# CAN.net
KiCad netlist of a schematic drawn in Altium Designer
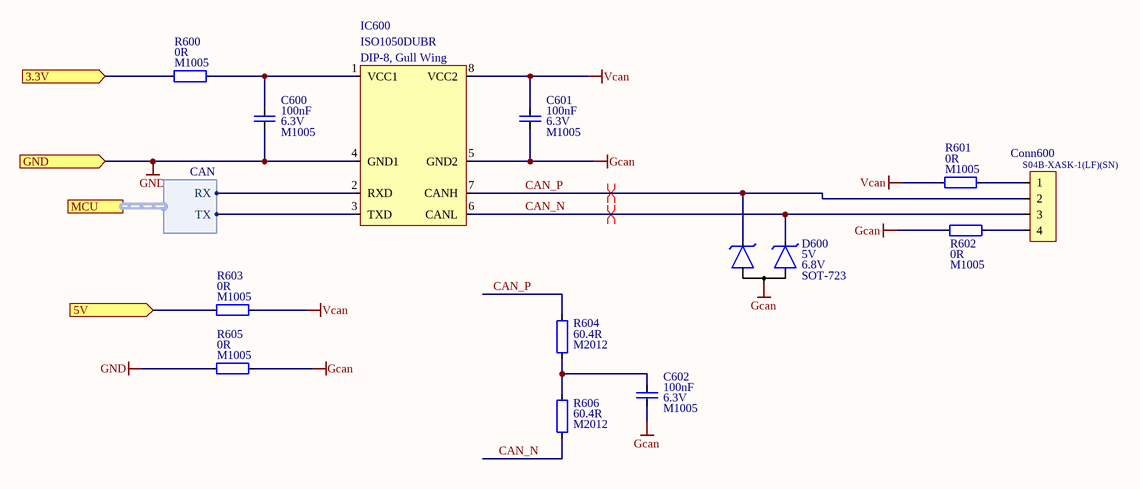
[diagram p0: CAN.SchDoc]

(export (version "E")
  (design (tool "Eeschema 10.0.6"))
  (components
    (comp (ref "C600")
      (value "100nF")
      (footprint "Capacitor_Ceramic_M1005_I0402")
      (description "Cap, Cer, 100nF, 6.3V, M1005")
      (fields
        (field (name "VOLTAGE") "6.3V")
        (field (name "MANUFACTURER PART NUMBER") "04026D104KAT4A")
        (field (name "MANUFACTURER") "Kyocera")
        (field (name "PACKAGE") "M1005")
      )
      (libsource (lib "Capacitor") (part "capacitor_ceramic"))
    )
    (comp (ref "C601")
      (value "100nF")
      (footprint "Capacitor_Ceramic_M1005_I0402")
      (description "Cap, Cer, 100nF, 6.3V, M1005")
      (fields
        (field (name "VOLTAGE") "6.3V")
        (field (name "MANUFACTURER PART NUMBER") "04026D104KAT4A")
        (field (name "MANUFACTURER") "Kyocera")
        (field (name "PACKAGE") "M1005")
      )
      (libsource (lib "Capacitor") (part "capacitor_ceramic"))
    )
    (comp (ref "C602")
      (value "100nF")
      (footprint "Capacitor_Ceramic_M1005_I0402")
      (description "Cap, Cer, 100nF, 6.3V, M1005")
      (fields
        (field (name "VOLTAGE") "6.3V")
        (field (name "MANUFACTURER PART NUMBER") "04026D104KAT4A")
        (field (name "MANUFACTURER") "Kyocera")
        (field (name "PACKAGE") "M1005")
      )
      (libsource (lib "Capacitor") (part "capacitor_ceramic"))
    )
    (comp (ref "Conn600")
      (value "Connector - 4P")
      (footprint "Connector, S04B-XASK-1")
      (description "Conn, JST, 4P, TH, XA, Side Entry")
      (fields
        (field (name "MANUFACTURER") "JST")
        (field (name "MANUFACTURER PART NUMBER") "S04B-XASK-1(LF)(SN)")
      )
      (libsource (lib "Connector - JST") (part "Connector - 4P"))
    )
    (comp (ref "D600")
      (value "Diode_Tvs_2P_Common_Anode")
      (footprint "Diode_SOT-723_2P_Common_Anode_Type_1")
      (description "Diode, TVS, 5V/6.8V, SOD-723")
      (fields
        (field (name "MANUFACTURER PART NUMBER") "DF3A6.8LFV,L3F")
        (field (name "MANUFACTURER") "Toshiba")
        (field (name "VOLTAGE, BREAK DOWN") "6.8V")
        (field (name "VOLTAGE, STAND OFF") "5V")
        (field (name "PACKAGE") "SOT-723")
      )
      (libsource (lib "Diode") (part "Diode_Tvs_2P_Common_Anode"))
    )
    (comp (ref "IC600")
      (value "CAN - Texas, ISO1050DUB")
      (footprint "DIP-8, Gull Wing")
      (description "IC, Interface, CAN, DIP-8, Gull Wing")
      (fields
        (field (name "MANUFACTURER") "Texas")
        (field (name "MANUFACTURER PART NUMBER") "ISO1050DUBR")
        (field (name "PACKAGE") "DIP-8, Gull Wing")
      )
      (libsource (lib "IC-Interface") (part "CAN - Texas, ISO1050DUB"))
    )
    (comp (ref "R600")
      (value "0R")
      (footprint "Resistor_Smd_M1005_I0402")
      (description "Res, 0R, M1005")
      (fields
        (field (name "MANUFACTURER") "Yageo")
        (field (name "MANUFACTURER PART NUMBER") "RC0402FR-070RL")
        (field (name "PACKAGE") "M1005")
      )
      (libsource (lib "Resistor") (part "Resistor"))
    )
    (comp (ref "R601")
      (value "0R")
      (footprint "Resistor_Smd_M1005_I0402")
      (description "Res, 0R, M1005")
      (fields
        (field (name "MANUFACTURER") "Yageo")
        (field (name "MANUFACTURER PART NUMBER") "RC0402FR-070RL")
        (field (name "PACKAGE") "M1005")
      )
      (libsource (lib "Resistor") (part "Resistor"))
    )
    (comp (ref "R602")
      (value "0R")
      (footprint "Resistor_Smd_M1005_I0402")
      (description "Res, 0R, M1005")
      (fields
        (field (name "MANUFACTURER") "Yageo")
        (field (name "MANUFACTURER PART NUMBER") "RC0402FR-070RL")
        (field (name "PACKAGE") "M1005")
      )
      (libsource (lib "Resistor") (part "Resistor"))
    )
    (comp (ref "R603")
      (value "0R")
      (footprint "Resistor_Smd_M1005_I0402")
      (description "Res, 0R, M1005")
      (fields
        (field (name "MANUFACTURER") "Yageo")
        (field (name "MANUFACTURER PART NUMBER") "RC0402FR-070RL")
        (field (name "PACKAGE") "M1005")
      )
      (libsource (lib "Resistor") (part "Resistor"))
    )
    (comp (ref "R604")
      (value "60.4R")
      (footprint "Resistor_Smd_M2012_I0805")
      (description "Res, 60.4R, 1%, M1005")
      (fields
        (field (name "TOLERANCE") "1%")
        (field (name "MANUFACTURER") "Yageo")
        (field (name "PACKAGE") "M2012")
      )
      (libsource (lib "Resistor") (part "Resistor"))
    )
    (comp (ref "R605")
      (value "0R")
      (footprint "Resistor_Smd_M1005_I0402")
      (description "Res, 0R, M1005")
      (fields
        (field (name "MANUFACTURER") "Yageo")
        (field (name "MANUFACTURER PART NUMBER") "RC0402FR-070RL")
        (field (name "PACKAGE") "M1005")
      )
      (libsource (lib "Resistor") (part "Resistor"))
    )
    (comp (ref "R606")
      (value "60.4R")
      (footprint "Resistor_Smd_M2012_I0805")
      (description "Res, 60.4R, 1%, M1005")
      (fields
        (field (name "TOLERANCE") "1%")
        (field (name "MANUFACTURER") "Yageo")
        (field (name "PACKAGE") "M2012")
      )
      (libsource (lib "Resistor") (part "Resistor"))
    )
  )
  (nets
    (net (code "2") (name "/3.3V") (class "Default")
      (node (ref "R600") (pin "1") (pinfunction "1_1") (pintype "passive"))
    )
    (net (code "3") (name "/5V") (class "Default")
      (node (ref "R603") (pin "1") (pinfunction "1_1") (pintype "passive"))
    )
    (net (code "4") (name "/CAN_N") (class "Default")
      (node (ref "Conn600") (pin "3") (pinfunction "3_3") (pintype "passive"))
      (node (ref "D600") (pin "C2") (pinfunction "C2_C2") (pintype "passive"))
      (node (ref "IC600") (pin "6") (pinfunction "CANL_6") (pintype "passive"))
      (node (ref "R606") (pin "2") (pinfunction "2_2") (pintype "passive"))
    )
    (net (code "5") (name "/CAN_P") (class "Default")
      (node (ref "Conn600") (pin "2") (pinfunction "2_2") (pintype "passive"))
      (node (ref "D600") (pin "C1") (pinfunction "C1_C1") (pintype "passive"))
      (node (ref "IC600") (pin "7") (pinfunction "CANH_7") (pintype "passive"))
      (node (ref "R604") (pin "1") (pinfunction "1_1") (pintype "passive"))
    )
    (net (code "6") (name "/RX") (class "Default")
      (node (ref "IC600") (pin "2") (pinfunction "RXD_2") (pintype "passive"))
    )
    (net (code "7") (name "/TX") (class "Default")
      (node (ref "IC600") (pin "3") (pinfunction "TXD_3") (pintype "passive"))
    )
    (net (code "9") (name "GND") (class "Default")
      (node (ref "C600") (pin "2") (pinfunction "2_2") (pintype "passive"))
      (node (ref "IC600") (pin "4") (pinfunction "GND1_4") (pintype "passive"))
      (node (ref "R605") (pin "1") (pinfunction "1_1") (pintype "passive"))
    )
    (net (code "10") (name "Gcan") (class "Default")
      (node (ref "C601") (pin "2") (pinfunction "2_2") (pintype "passive"))
      (node (ref "C602") (pin "2") (pinfunction "2_2") (pintype "passive"))
      (node (ref "D600") (pin "A") (pinfunction "A_A") (pintype "passive"))
      (node (ref "IC600") (pin "5") (pinfunction "GND2_5") (pintype "passive"))
      (node (ref "R602") (pin "1") (pinfunction "1_1") (pintype "passive"))
      (node (ref "R605") (pin "2") (pinfunction "2_2") (pintype "passive"))
    )
    (net (code "11") (name "Net-(C602-Pad1)") (class "Default")
      (node (ref "C602") (pin "1") (pinfunction "1_1") (pintype "passive"))
      (node (ref "R604") (pin "2") (pinfunction "2_2") (pintype "passive"))
      (node (ref "R606") (pin "1") (pinfunction "1_1") (pintype "passive"))
    )
    (net (code "12") (name "Net-(Conn600-Pad1)") (class "Default")
      (node (ref "Conn600") (pin "1") (pinfunction "1_1") (pintype "passive"))
      (node (ref "R601") (pin "2") (pinfunction "2_2") (pintype "passive"))
    )
    (net (code "13") (name "Net-(Conn600-Pad4)") (class "Default")
      (node (ref "Conn600") (pin "4") (pinfunction "4_4") (pintype "passive"))
      (node (ref "R602") (pin "2") (pinfunction "2_2") (pintype "passive"))
    )
    (net (code "14") (name "Net-(IC600-VCC1)") (class "Default")
      (node (ref "C600") (pin "1") (pinfunction "1_1") (pintype "passive"))
      (node (ref "IC600") (pin "1") (pinfunction "VCC1_1") (pintype "passive"))
      (node (ref "R600") (pin "2") (pinfunction "2_2") (pintype "passive"))
    )
    (net (code "15") (name "Vcan") (class "Default")
      (node (ref "C601") (pin "1") (pinfunction "1_1") (pintype "passive"))
      (node (ref "IC600") (pin "8") (pinfunction "VCC2_8") (pintype "passive"))
      (node (ref "R601") (pin "1") (pinfunction "1_1") (pintype "passive"))
      (node (ref "R603") (pin "2") (pinfunction "2_2") (pintype "passive"))
    )
  )
)
